# WindHack.net
KiCad netlist of a schematic drawn in EAGLE
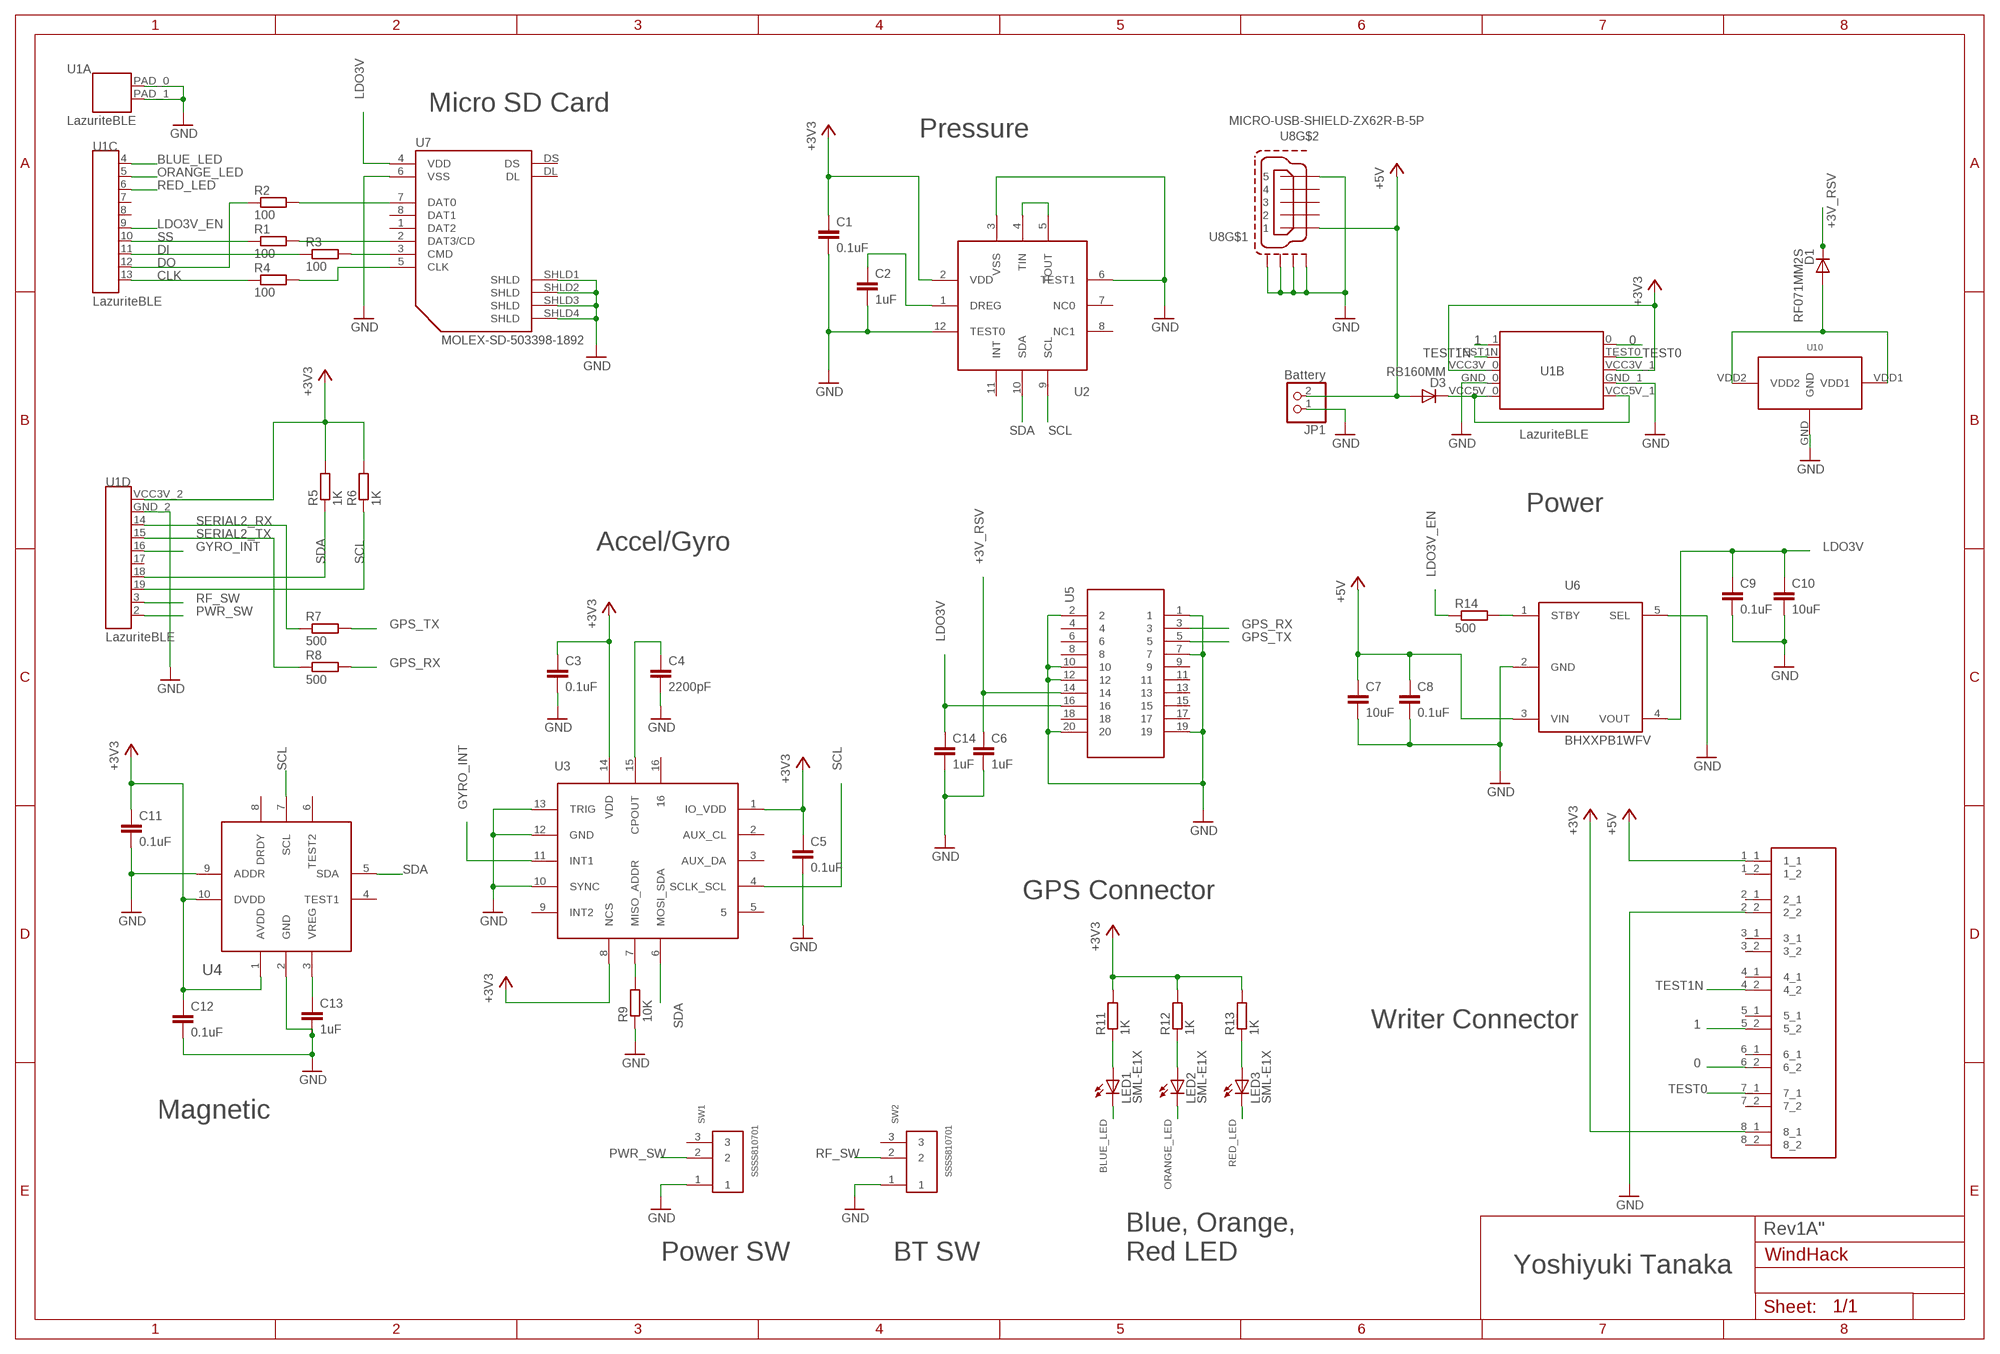
[diagram p0: schematic, sheet 1]

(export (version "E")
  (design (tool "Eeschema 10.0.6"))
  (components
    (comp (ref "C1")
      (value "0.1uF")
      (footprint "eagle-import:C0603")
      (libsource (lib "eagle-import") (part "C-EUC0603"))
    )
    (comp (ref "C2")
      (value "1uF")
      (footprint "eagle-import:C0603")
      (libsource (lib "eagle-import") (part "C-EUC0603"))
    )
    (comp (ref "C3")
      (value "0.1uF")
      (footprint "eagle-import:C0603")
      (libsource (lib "eagle-import") (part "C-EUC0603"))
    )
    (comp (ref "C4")
      (value "2200pF")
      (footprint "eagle-import:C0603")
      (libsource (lib "eagle-import") (part "C-EUC0603"))
    )
    (comp (ref "C5")
      (value "0.1uF")
      (footprint "eagle-import:C0603")
      (libsource (lib "eagle-import") (part "C-EUC0603"))
    )
    (comp (ref "C6")
      (value "1uF")
      (footprint "eagle-import:C0603")
      (libsource (lib "eagle-import") (part "C-EUC0603"))
    )
    (comp (ref "C7")
      (value "10uF")
      (footprint "eagle-import:C0603")
      (libsource (lib "eagle-import") (part "C-EUC0603"))
    )
    (comp (ref "C8")
      (value "0.1uF")
      (footprint "eagle-import:C0603")
      (libsource (lib "eagle-import") (part "C-EUC0603"))
    )
    (comp (ref "C9")
      (value "0.1uF")
      (footprint "eagle-import:C0603")
      (libsource (lib "eagle-import") (part "C-EUC0603"))
    )
    (comp (ref "C10")
      (value "10uF")
      (footprint "eagle-import:C0603")
      (libsource (lib "eagle-import") (part "C-EUC0603"))
    )
    (comp (ref "C11")
      (value "0.1uF")
      (footprint "eagle-import:C0603")
      (libsource (lib "eagle-import") (part "C-EUC0603"))
    )
    (comp (ref "C12")
      (value "0.1uF")
      (footprint "eagle-import:C0603")
      (libsource (lib "eagle-import") (part "C-EUC0603"))
    )
    (comp (ref "C13")
      (value "1uF")
      (footprint "eagle-import:C0603")
      (libsource (lib "eagle-import") (part "C-EUC0603"))
    )
    (comp (ref "C14")
      (value "1uF")
      (footprint "eagle-import:C0603")
      (libsource (lib "eagle-import") (part "C-EUC0603"))
    )
    (comp (ref "D1")
      (value "RF071MM2S")
      (footprint "eagle-import:RF071MM2S")
      (libsource (lib "eagle-import") (part "RF071MM2S"))
    )
    (comp (ref "D3")
      (value "RB160MM")
      (footprint "eagle-import:RB160MM-30")
      (libsource (lib "eagle-import") (part "RB160MM"))
    )
    (comp (ref "JP1")
      (value "Battery")
      (footprint "eagle-import:1X02")
      (libsource (lib "eagle-import") (part "PINHD-1X2"))
    )
    (comp (ref "LED1")
      (value "SML-E1X")
      (footprint "eagle-import:SML-E1X")
      (libsource (lib "eagle-import") (part "SML-E1X"))
    )
    (comp (ref "LED2")
      (value "SML-E1X")
      (footprint "eagle-import:SML-E1X")
      (libsource (lib "eagle-import") (part "SML-E1X"))
    )
    (comp (ref "LED3")
      (value "SML-E1X")
      (footprint "eagle-import:SML-E1X")
      (libsource (lib "eagle-import") (part "SML-E1X"))
    )
    (comp (ref "R1")
      (value "100")
      (footprint "eagle-import:R0603")
      (libsource (lib "eagle-import") (part "R-EU_R0603"))
    )
    (comp (ref "R2")
      (value "100")
      (footprint "eagle-import:R0603")
      (libsource (lib "eagle-import") (part "R-EU_R0603"))
    )
    (comp (ref "R3")
      (value "100")
      (footprint "eagle-import:R0603")
      (libsource (lib "eagle-import") (part "R-EU_R0603"))
    )
    (comp (ref "R4")
      (value "100")
      (footprint "eagle-import:R0603")
      (libsource (lib "eagle-import") (part "R-EU_R0603"))
    )
    (comp (ref "R5")
      (value "1K")
      (footprint "eagle-import:R0603")
      (libsource (lib "eagle-import") (part "R-EU_R0603"))
    )
    (comp (ref "R6")
      (value "1K")
      (footprint "eagle-import:R0603")
      (libsource (lib "eagle-import") (part "R-EU_R0603"))
    )
    (comp (ref "R7")
      (value "500")
      (footprint "eagle-import:R0603")
      (libsource (lib "eagle-import") (part "R-EU_R0603"))
    )
    (comp (ref "R8")
      (value "500")
      (footprint "eagle-import:R0603")
      (libsource (lib "eagle-import") (part "R-EU_R0603"))
    )
    (comp (ref "R9")
      (value "10K")
      (footprint "eagle-import:R0603")
      (libsource (lib "eagle-import") (part "R-EU_R0603"))
    )
    (comp (ref "R11")
      (value "1K")
      (footprint "eagle-import:R0603")
      (libsource (lib "eagle-import") (part "R-EU_R0603"))
    )
    (comp (ref "R12")
      (value "1K")
      (footprint "eagle-import:R0603")
      (libsource (lib "eagle-import") (part "R-EU_R0603"))
    )
    (comp (ref "R13")
      (value "1K")
      (footprint "eagle-import:R0603")
      (libsource (lib "eagle-import") (part "R-EU_R0603"))
    )
    (comp (ref "R14")
      (value "500")
      (footprint "eagle-import:R0603")
      (libsource (lib "eagle-import") (part "R-EU_R0603"))
    )
    (comp (ref "SW1")
      (value "SSSS810701")
      (footprint "eagle-import:SSSS810701")
      (libsource (lib "eagle-import") (part "SSSS810701"))
    )
    (comp (ref "SW2")
      (value "SSSS810701")
      (footprint "eagle-import:SSSS810701")
      (libsource (lib "eagle-import") (part "SSSS810701"))
    )
    (comp (ref "U$1")
      (value "XB-1-X")
      (footprint "eagle-import:XB-1-X")
      (libsource (lib "eagle-import") (part "XB-1-X"))
    )
    (comp (ref "U1")
      (value "LazuriteBLE")
      (footprint "eagle-import:LAZURITE920J")
      (libsource (lib "eagle-import") (part "LAZURITE920JLAZURITE920J"))
    )
    (comp (ref "U2")
      (value "BM1383AGLV")
      (footprint "eagle-import:BM1383AGLV")
      (libsource (lib "eagle-import") (part "BM1383AGLV"))
    )
    (comp (ref "U3")
      (value "KXG03")
      (footprint "eagle-import:KXG03")
      (libsource (lib "eagle-import") (part "KXG03"))
    )
    (comp (ref "U4")
      (value "BM1422AGMV")
      (footprint "eagle-import:BM1422AGMV")
      (libsource (lib "eagle-import") (part "BM1422AGMV"))
    )
    (comp (ref "U5")
      (value "DF40C-20DS-0.4V")
      (footprint "eagle-import:DF40C-20DS-0.4V")
      (libsource (lib "eagle-import") (part "DF40C-20DS-0.4V"))
    )
    (comp (ref "U6")
      (value "BHXXPB1WFV")
      (footprint "eagle-import:HVSOF5")
      (libsource (lib "eagle-import") (part "BHXXPB1WFV"))
    )
    (comp (ref "U7")
      (value "MOLEX-SD-503398-1892")
      (footprint "eagle-import:MOLEX-SD-503398-003")
      (libsource (lib "eagle-import") (part "MOLEX-SD-503398-1892"))
    )
    (comp (ref "U8")
      (value "MICRO-USB-SHIELD-ZX62R-B-5P")
      (footprint "eagle-import:ZX62R-B-5P")
      (libsource (lib "eagle-import") (part "MICRO-USB-SHIELD-ZX62R-B-5P"))
    )
    (comp (ref "U10")
      (value "BK-913")
      (footprint "eagle-import:BK-913")
      (libsource (lib "eagle-import") (part "BK-913"))
    )
  )
  (nets
    (net (code "1") (name "+3V3") (class "Default")
      (node (ref "C1") (pin "1") (pinfunction "1_1") (pintype "passive"))
      (node (ref "C11") (pin "1") (pinfunction "1_1") (pintype "passive"))
      (node (ref "C12") (pin "1") (pinfunction "1_1") (pintype "passive"))
      (node (ref "C3") (pin "1") (pinfunction "1_1") (pintype "passive"))
      (node (ref "C5") (pin "1") (pinfunction "1_1") (pintype "passive"))
      (node (ref "R11") (pin "2") (pinfunction "2_2") (pintype "passive"))
      (node (ref "R12") (pin "2") (pinfunction "2_2") (pintype "passive"))
      (node (ref "R13") (pin "2") (pinfunction "2_2") (pintype "passive"))
      (node (ref "R5") (pin "2") (pinfunction "2_2") (pintype "passive"))
      (node (ref "R6") (pin "2") (pinfunction "2_2") (pintype "passive"))
      (node (ref "U$1") (pin "8_1") (pinfunction "8_1_8_1") (pintype "bidirectional"))
      (node (ref "U1") (pin "VCC3V_0") (pinfunction "VCC3V_0_VCC3V_0") (pintype "passive"))
      (node (ref "U1") (pin "VCC3V_1") (pinfunction "VCC3V_1_VCC3V_1") (pintype "passive"))
      (node (ref "U1") (pin "VCC3V_2") (pinfunction "VCC3V_2_VCC3V_2") (pintype "passive"))
      (node (ref "U2") (pin "2") (pinfunction "VDD_2") (pintype "power_in"))
      (node (ref "U3") (pin "1") (pinfunction "IO_VDD_1") (pintype "power_in"))
      (node (ref "U3") (pin "14") (pinfunction "VDD_14") (pintype "power_in"))
      (node (ref "U3") (pin "8") (pinfunction "NCS_8") (pintype "bidirectional"))
      (node (ref "U4") (pin "1") (pinfunction "AVDD_1") (pintype "power_in"))
      (node (ref "U4") (pin "10") (pinfunction "DVDD_10") (pintype "power_in"))
    )
    (net (code "2") (name "+5V") (class "Default")
      (node (ref "C7") (pin "1") (pinfunction "1_1") (pintype "passive"))
      (node (ref "C8") (pin "1") (pinfunction "1_1") (pintype "passive"))
      (node (ref "D3") (pin "A") (pinfunction "A_A") (pintype "passive"))
      (node (ref "JP1") (pin "2") (pinfunction "2_2") (pintype "passive"))
      (node (ref "U$1") (pin "1_1") (pinfunction "1_1_1_1") (pintype "bidirectional"))
      (node (ref "U6") (pin "3") (pinfunction "VIN_3") (pintype "bidirectional"))
      (node (ref "U8") (pin "1") (pinfunction "1_1") (pintype "input"))
    )
    (net (code "3") (name "/+3V_RSV") (class "Default")
      (node (ref "C6") (pin "1") (pinfunction "1_1") (pintype "passive"))
      (node (ref "D1") (pin "C") (pinfunction "C_C") (pintype "passive"))
      (node (ref "U5") (pin "14") (pinfunction "14_14") (pintype "bidirectional"))
    )
    (net (code "4") (name "/0") (class "Default")
      (node (ref "U$1") (pin "6_2") (pinfunction "6_2_6_2") (pintype "bidirectional"))
      (node (ref "U1") (pin "0") (pinfunction "0_0") (pintype "passive"))
    )
    (net (code "5") (name "/1") (class "Default")
      (node (ref "U$1") (pin "5_2") (pinfunction "5_2_5_2") (pintype "bidirectional"))
      (node (ref "U1") (pin "1") (pinfunction "1_1") (pintype "passive"))
    )
    (net (code "6") (name "/BLUE_LED") (class "Default")
      (node (ref "LED1") (pin "C") (pinfunction "C_C") (pintype "passive"))
      (node (ref "U1") (pin "4") (pinfunction "4_4") (pintype "passive"))
    )
    (net (code "7") (name "/CLK") (class "Default")
      (node (ref "R4") (pin "1") (pinfunction "1_1") (pintype "passive"))
      (node (ref "U1") (pin "13") (pinfunction "13_13") (pintype "passive"))
    )
    (net (code "8") (name "/DI") (class "Default")
      (node (ref "R3") (pin "1") (pinfunction "1_1") (pintype "passive"))
      (node (ref "U1") (pin "11") (pinfunction "11_11") (pintype "passive"))
    )
    (net (code "9") (name "/DO") (class "Default")
      (node (ref "R2") (pin "1") (pinfunction "1_1") (pintype "passive"))
      (node (ref "U1") (pin "12") (pinfunction "12_12") (pintype "passive"))
    )
    (net (code "10") (name "/GPS_RX") (class "Default")
      (node (ref "R8") (pin "2") (pinfunction "2_2") (pintype "passive"))
      (node (ref "U5") (pin "3") (pinfunction "3_3") (pintype "bidirectional"))
    )
    (net (code "11") (name "/GPS_TX") (class "Default")
      (node (ref "R7") (pin "2") (pinfunction "2_2") (pintype "passive"))
      (node (ref "U5") (pin "5") (pinfunction "5_5") (pintype "bidirectional"))
    )
    (net (code "12") (name "/GYRO_INT") (class "Default")
      (node (ref "U1") (pin "16") (pinfunction "16_16") (pintype "passive"))
      (node (ref "U3") (pin "11") (pinfunction "INT1_11") (pintype "output"))
    )
    (net (code "13") (name "/LDO3V") (class "Default")
      (node (ref "C10") (pin "1") (pinfunction "1_1") (pintype "passive"))
      (node (ref "C14") (pin "1") (pinfunction "1_1") (pintype "passive"))
      (node (ref "C9") (pin "1") (pinfunction "1_1") (pintype "passive"))
      (node (ref "U5") (pin "16") (pinfunction "16_16") (pintype "bidirectional"))
      (node (ref "U6") (pin "4") (pinfunction "VOUT_4") (pintype "bidirectional"))
      (node (ref "U7") (pin "4") (pinfunction "VDD_4") (pintype "power_in"))
    )
    (net (code "14") (name "/LDO3V_EN") (class "Default")
      (node (ref "R14") (pin "1") (pinfunction "1_1") (pintype "passive"))
      (node (ref "U1") (pin "9") (pinfunction "9_9") (pintype "passive"))
    )
    (net (code "15") (name "/ORANGE_LED") (class "Default")
      (node (ref "LED2") (pin "C") (pinfunction "C_C") (pintype "passive"))
      (node (ref "U1") (pin "5") (pinfunction "5_5") (pintype "passive"))
    )
    (net (code "16") (name "/PWR_SW") (class "Default")
      (node (ref "SW1") (pin "2") (pinfunction "2_2") (pintype "bidirectional"))
      (node (ref "U1") (pin "2") (pinfunction "2_2") (pintype "passive"))
    )
    (net (code "17") (name "/RED_LED") (class "Default")
      (node (ref "LED3") (pin "C") (pinfunction "C_C") (pintype "passive"))
      (node (ref "U1") (pin "6") (pinfunction "6_6") (pintype "passive"))
    )
    (net (code "18") (name "/RF_SW") (class "Default")
      (node (ref "SW2") (pin "2") (pinfunction "2_2") (pintype "bidirectional"))
      (node (ref "U1") (pin "3") (pinfunction "3_3") (pintype "passive"))
    )
    (net (code "19") (name "/SCL") (class "Default")
      (node (ref "R6") (pin "1") (pinfunction "1_1") (pintype "passive"))
      (node (ref "U1") (pin "19") (pinfunction "19_19") (pintype "passive"))
      (node (ref "U2") (pin "9") (pinfunction "SCL_9") (pintype "bidirectional"))
      (node (ref "U3") (pin "4") (pinfunction "SCLK_SCL_4") (pintype "input"))
      (node (ref "U4") (pin "7") (pinfunction "SCL_7") (pintype "input"))
    )
    (net (code "20") (name "/SDA") (class "Default")
      (node (ref "R5") (pin "1") (pinfunction "1_1") (pintype "passive"))
      (node (ref "U1") (pin "18") (pinfunction "18_18") (pintype "passive"))
      (node (ref "U2") (pin "10") (pinfunction "SDA_10") (pintype "bidirectional"))
      (node (ref "U3") (pin "6") (pinfunction "MOSI_SDA_6") (pintype "bidirectional"))
      (node (ref "U4") (pin "5") (pinfunction "SDA_5") (pintype "bidirectional"))
    )
    (net (code "21") (name "/SERIAL2_RX") (class "Default")
      (node (ref "R7") (pin "1") (pinfunction "1_1") (pintype "passive"))
      (node (ref "U1") (pin "14") (pinfunction "14_14") (pintype "passive"))
    )
    (net (code "22") (name "/SERIAL2_TX") (class "Default")
      (node (ref "R8") (pin "1") (pinfunction "1_1") (pintype "passive"))
      (node (ref "U1") (pin "15") (pinfunction "15_15") (pintype "passive"))
    )
    (net (code "23") (name "/SS") (class "Default")
      (node (ref "R1") (pin "1") (pinfunction "1_1") (pintype "passive"))
      (node (ref "U1") (pin "10") (pinfunction "10_10") (pintype "passive"))
    )
    (net (code "24") (name "/TEST0") (class "Default")
      (node (ref "U$1") (pin "7_1") (pinfunction "7_1_7_1") (pintype "bidirectional"))
      (node (ref "U1") (pin "TEST0") (pinfunction "TEST0_TEST0") (pintype "passive"))
    )
    (net (code "25") (name "/TEST1N") (class "Default")
      (node (ref "U$1") (pin "4_2") (pinfunction "4_2_4_2") (pintype "bidirectional"))
      (node (ref "U1") (pin "TEST1N") (pinfunction "TEST1N_TEST1N") (pintype "passive"))
    )
    (net (code "26") (name "GND") (class "Default")
      (node (ref "C1") (pin "2") (pinfunction "2_2") (pintype "passive"))
      (node (ref "C10") (pin "2") (pinfunction "2_2") (pintype "passive"))
      (node (ref "C11") (pin "2") (pinfunction "2_2") (pintype "passive"))
      (node (ref "C12") (pin "2") (pinfunction "2_2") (pintype "passive"))
      (node (ref "C13") (pin "2") (pinfunction "2_2") (pintype "passive"))
      (node (ref "C14") (pin "2") (pinfunction "2_2") (pintype "passive"))
      (node (ref "C2") (pin "2") (pinfunction "2_2") (pintype "passive"))
      (node (ref "C3") (pin "2") (pinfunction "2_2") (pintype "passive"))
      (node (ref "C4") (pin "2") (pinfunction "2_2") (pintype "passive"))
      (node (ref "C5") (pin "2") (pinfunction "2_2") (pintype "passive"))
      (node (ref "C6") (pin "2") (pinfunction "2_2") (pintype "passive"))
      (node (ref "C7") (pin "2") (pinfunction "2_2") (pintype "passive"))
      (node (ref "C8") (pin "2") (pinfunction "2_2") (pintype "passive"))
      (node (ref "C9") (pin "2") (pinfunction "2_2") (pintype "passive"))
      (node (ref "JP1") (pin "1") (pinfunction "1_1") (pintype "passive"))
      (node (ref "R9") (pin "1") (pinfunction "1_1") (pintype "passive"))
      (node (ref "SW1") (pin "1") (pinfunction "1_1") (pintype "bidirectional"))
      (node (ref "SW2") (pin "1") (pinfunction "1_1") (pintype "bidirectional"))
      (node (ref "U$1") (pin "2_2") (pinfunction "2_2_2_2") (pintype "bidirectional"))
      (node (ref "U1") (pin "GND_0") (pinfunction "GND_0_GND_0") (pintype "passive"))
      (node (ref "U1") (pin "GND_1") (pinfunction "GND_1_GND_1") (pintype "passive"))
      (node (ref "U1") (pin "GND_2") (pinfunction "GND_2_GND_2") (pintype "passive"))
      (node (ref "U1") (pin "PAD_0") (pinfunction "PAD_0_PAD_0") (pintype "passive"))
      (node (ref "U1") (pin "PAD_1") (pinfunction "PAD_1_PAD_1") (pintype "passive"))
      (node (ref "U10") (pin "GND") (pinfunction "GND_GND") (pintype "power_in"))
      (node (ref "U2") (pin "12") (pinfunction "TEST0_12") (pintype "bidirectional"))
      (node (ref "U2") (pin "3") (pinfunction "VSS_3") (pintype "power_in"))
      (node (ref "U2") (pin "6") (pinfunction "TEST1_6") (pintype "bidirectional"))
      (node (ref "U3") (pin "10") (pinfunction "SYNC_10") (pintype "bidirectional"))
      (node (ref "U3") (pin "12") (pinfunction "GND_12") (pintype "power_in"))
      (node (ref "U3") (pin "13") (pinfunction "TRIG_13") (pintype "input"))
      (node (ref "U4") (pin "2") (pinfunction "GND_2") (pintype "power_in"))
      (node (ref "U4") (pin "9") (pinfunction "ADDR_9") (pintype "input"))
      (node (ref "U5") (pin "1") (pinfunction "1_1") (pintype "bidirectional"))
      (node (ref "U5") (pin "10") (pinfunction "10_10") (pintype "bidirectional"))
      (node (ref "U5") (pin "12") (pinfunction "12_12") (pintype "bidirectional"))
      (node (ref "U5") (pin "19") (pinfunction "19_19") (pintype "bidirectional"))
      (node (ref "U5") (pin "2") (pinfunction "2_2") (pintype "bidirectional"))
      (node (ref "U5") (pin "20") (pinfunction "20_20") (pintype "bidirectional"))
      (node (ref "U5") (pin "7") (pinfunction "7_7") (pintype "bidirectional"))
      (node (ref "U6") (pin "2") (pinfunction "GND_2") (pintype "bidirectional"))
      (node (ref "U6") (pin "5") (pinfunction "SEL_5") (pintype "bidirectional"))
      (node (ref "U7") (pin "6") (pinfunction "VSS_6") (pintype "power_in"))
      (node (ref "U7") (pin "SHLD1") (pinfunction "SHLD_SHLD1") (pintype "power_in"))
      (node (ref "U7") (pin "SHLD2") (pinfunction "SHLD_SHLD2") (pintype "power_in"))
      (node (ref "U7") (pin "SHLD3") (pinfunction "SHLD_SHLD3") (pintype "power_in"))
      (node (ref "U7") (pin "SHLD4") (pinfunction "SHLD_SHLD4") (pintype "power_in"))
      (node (ref "U8") (pin "5") (pinfunction "5_5") (pintype "input"))
      (node (ref "U8") (pin "M1") (pinfunction "S1_M1") (pintype "passive"))
      (node (ref "U8") (pin "M2") (pinfunction "S2_M2") (pintype "passive"))
      (node (ref "U8") (pin "M3") (pinfunction "S3_M3") (pintype "passive"))
      (node (ref "U8") (pin "M4") (pinfunction "S4_M4") (pintype "passive"))
    )
    (net (code "27") (name "Net-(D1-PadA)") (class "Default")
      (node (ref "D1") (pin "A") (pinfunction "A_A") (pintype "passive"))
      (node (ref "U10") (pin "VDD1") (pinfunction "VDD1_VDD1") (pintype "power_in"))
      (node (ref "U10") (pin "VDD2") (pinfunction "VDD2_VDD2") (pintype "power_in"))
    )
    (net (code "28") (name "Net-(D3-PadC)") (class "Default")
      (node (ref "D3") (pin "C") (pinfunction "C_C") (pintype "passive"))
      (node (ref "U1") (pin "VCC5V_0") (pinfunction "VCC5V_0_VCC5V_0") (pintype "passive"))
      (node (ref "U1") (pin "VCC5V_1") (pinfunction "VCC5V_1_VCC5V_1") (pintype "passive"))
    )
    (net (code "29") (name "Net-(LED1-PadA)") (class "Default")
      (node (ref "LED1") (pin "A") (pinfunction "A_A") (pintype "passive"))
      (node (ref "R11") (pin "1") (pinfunction "1_1") (pintype "passive"))
    )
    (net (code "30") (name "Net-(LED2-PadA)") (class "Default")
      (node (ref "LED2") (pin "A") (pinfunction "A_A") (pintype "passive"))
      (node (ref "R12") (pin "1") (pinfunction "1_1") (pintype "passive"))
    )
    (net (code "31") (name "Net-(LED3-PadA)") (class "Default")
      (node (ref "LED3") (pin "A") (pinfunction "A_A") (pintype "passive"))
      (node (ref "R13") (pin "1") (pinfunction "1_1") (pintype "passive"))
    )
    (net (code "32") (name "Net-(U2-DREG)") (class "Default")
      (node (ref "C2") (pin "1") (pinfunction "1_1") (pintype "passive"))
      (node (ref "U2") (pin "1") (pinfunction "DREG_1") (pintype "bidirectional"))
    )
    (net (code "33") (name "Net-(U2-TIN)") (class "Default")
      (node (ref "U2") (pin "4") (pinfunction "TIN_4") (pintype "input"))
      (node (ref "U2") (pin "5") (pinfunction "TOUT_5") (pintype "output"))
    )
    (net (code "34") (name "Net-(U3-CPOUT)") (class "Default")
      (node (ref "C4") (pin "1") (pinfunction "1_1") (pintype "passive"))
      (node (ref "U3") (pin "15") (pinfunction "CPOUT_15") (pintype "bidirectional"))
    )
    (net (code "35") (name "Net-(U3-MISO_ADDR)") (class "Default")
      (node (ref "R9") (pin "2") (pinfunction "2_2") (pintype "passive"))
      (node (ref "U3") (pin "7") (pinfunction "MISO_ADDR_7") (pintype "bidirectional"))
    )
    (net (code "36") (name "Net-(U4-VREG)") (class "Default")
      (node (ref "C13") (pin "1") (pinfunction "1_1") (pintype "passive"))
      (node (ref "U4") (pin "3") (pinfunction "VREG_3") (pintype "output"))
    )
    (net (code "37") (name "Net-(U6-STBY)") (class "Default")
      (node (ref "R14") (pin "2") (pinfunction "2_2") (pintype "passive"))
      (node (ref "U6") (pin "1") (pinfunction "STBY_1") (pintype "bidirectional"))
    )
    (net (code "38") (name "Net-(U7-CLK)") (class "Default")
      (node (ref "R4") (pin "2") (pinfunction "2_2") (pintype "passive"))
      (node (ref "U7") (pin "5") (pinfunction "CLK_5") (pintype "bidirectional"))
    )
    (net (code "39") (name "Net-(U7-CMD)") (class "Default")
      (node (ref "R3") (pin "2") (pinfunction "2_2") (pintype "passive"))
      (node (ref "U7") (pin "3") (pinfunction "CMD_3") (pintype "bidirectional"))
    )
    (net (code "40") (name "Net-(U7-DAT0)") (class "Default")
      (node (ref "R2") (pin "2") (pinfunction "2_2") (pintype "passive"))
      (node (ref "U7") (pin "7") (pinfunction "DAT0_7") (pintype "bidirectional"))
    )
    (net (code "41") (name "Net-(U7-DAT3{slash}CD)") (class "Default")
      (node (ref "R1") (pin "2") (pinfunction "2_2") (pintype "passive"))
      (node (ref "U7") (pin "2") (pinfunction "DAT3/CD_2") (pintype "bidirectional"))
    )
    (net (code "42") (name "unconnected-(SW1-Pad3)") (class "Default")
      (node (ref "SW1") (pin "3") (pinfunction "3_3") (pintype "bidirectional"))
    )
    (net (code "43") (name "unconnected-(SW2-Pad3)") (class "Default")
      (node (ref "SW2") (pin "3") (pinfunction "3_3") (pintype "bidirectional"))
    )
    (net (code "44") (name "unconnected-(U$1-Pad1_2)") (class "Default")
      (node (ref "U$1") (pin "1_2") (pinfunction "1_2_1_2") (pintype "bidirectional"))
    )
    (net (code "45") (name "unconnected-(U$1-Pad2_1)") (class "Default")
      (node (ref "U$1") (pin "2_1") (pinfunction "2_1_2_1") (pintype "bidirectional"))
    )
    (net (code "46") (name "unconnected-(U$1-Pad3_1)") (class "Default")
      (node (ref "U$1") (pin "3_1") (pinfunction "3_1_3_1") (pintype "bidirectional"))
    )
    (net (code "47") (name "unconnected-(U$1-Pad3_2)") (class "Default")
      (node (ref "U$1") (pin "3_2") (pinfunction "3_2_3_2") (pintype "bidirectional"))
    )
    (net (code "48") (name "unconnected-(U$1-Pad4_1)") (class "Default")
      (node (ref "U$1") (pin "4_1") (pinfunction "4_1_4_1") (pintype "bidirectional"))
    )
    (net (code "49") (name "unconnected-(U$1-Pad5_1)") (class "Default")
      (node (ref "U$1") (pin "5_1") (pinfunction "5_1_5_1") (pintype "bidirectional"))
    )
    (net (code "50") (name "unconnected-(U$1-Pad6_1)") (class "Default")
      (node (ref "U$1") (pin "6_1") (pinfunction "6_1_6_1") (pintype "bidirectional"))
    )
    (net (code "51") (name "unconnected-(U$1-Pad7_2)") (class "Default")
      (node (ref "U$1") (pin "7_2") (pinfunction "7_2_7_2") (pintype "bidirectional"))
    )
    (net (code "52") (name "unconnected-(U$1-Pad8_2)") (class "Default")
      (node (ref "U$1") (pin "8_2") (pinfunction "8_2_8_2") (pintype "bidirectional"))
    )
    (net (code "53") (name "unconnected-(U1-Pad7)") (class "Default")
      (node (ref "U1") (pin "7") (pinfunction "7_7") (pintype "passive"))
    )
    (net (code "54") (name "unconnected-(U1-Pad8)") (class "Default")
      (node (ref "U1") (pin "8") (pinfunction "8_8") (pintype "passive"))
    )
    (net (code "55") (name "unconnected-(U1-Pad17)") (class "Default")
      (node (ref "U1") (pin "17") (pinfunction "17_17") (pintype "passive"))
    )
    (net (code "56") (name "unconnected-(U2-INT-Pad11)") (class "Default")
      (node (ref "U2") (pin "11") (pinfunction "INT_11") (pintype "output"))
    )
    (net (code "57") (name "unconnected-(U2-NC0-Pad7)") (class "Default")
      (node (ref "U2") (pin "7") (pinfunction "NC0_7") (pintype "no_connect"))
    )
    (net (code "58") (name "unconnected-(U2-NC1-Pad8)") (class "Default")
      (node (ref "U2") (pin "8") (pinfunction "NC1_8") (pintype "no_connect"))
    )
    (net (code "59") (name "unconnected-(U3-AUX_CL-Pad2)") (class "Default")
      (node (ref "U3") (pin "2") (pinfunction "AUX_CL_2") (pintype "input"))
    )
    (net (code "60") (name "unconnected-(U3-AUX_DA-Pad3)") (class "Default")
      (node (ref "U3") (pin "3") (pinfunction "AUX_DA_3") (pintype "bidirectional"))
    )
    (net (code "61") (name "unconnected-(U3-INT2-Pad9)") (class "Default")
      (node (ref "U3") (pin "9") (pinfunction "INT2_9") (pintype "output"))
    )
    (net (code "62") (name "unconnected-(U3-Pad5)") (class "Default")
      (node (ref "U3") (pin "5") (pinfunction "5_5") (pintype "no_connect"))
    )
    (net (code "63") (name "unconnected-(U3-Pad16)") (class "Default")
      (node (ref "U3") (pin "16") (pinfunction "16_16") (pintype "no_connect"))
    )
    (net (code "64") (name "unconnected-(U4-DRDY-Pad8)") (class "Default")
      (node (ref "U4") (pin "8") (pinfunction "DRDY_8") (pintype "output"))
    )
    (net (code "65") (name "unconnected-(U4-TEST1-Pad4)") (class "Default")
      (node (ref "U4") (pin "4") (pinfunction "TEST1_4") (pintype "no_connect"))
    )
    (net (code "66") (name "unconnected-(U4-TEST2-Pad6)") (class "Default")
      (node (ref "U4") (pin "6") (pinfunction "TEST2_6") (pintype "no_connect"))
    )
    (net (code "67") (name "unconnected-(U5-Pad4)") (class "Default")
      (node (ref "U5") (pin "4") (pinfunction "4_4") (pintype "bidirectional"))
    )
    (net (code "68") (name "unconnected-(U5-Pad6)") (class "Default")
      (node (ref "U5") (pin "6") (pinfunction "6_6") (pintype "bidirectional"))
    )
    (net (code "69") (name "unconnected-(U5-Pad8)") (class "Default")
      (node (ref "U5") (pin "8") (pinfunction "8_8") (pintype "bidirectional"))
    )
    (net (code "70") (name "unconnected-(U5-Pad9)") (class "Default")
      (node (ref "U5") (pin "9") (pinfunction "9_9") (pintype "bidirectional"))
    )
    (net (code "71") (name "unconnected-(U5-Pad11)") (class "Default")
      (node (ref "U5") (pin "11") (pinfunction "11_11") (pintype "bidirectional"))
    )
    (net (code "72") (name "unconnected-(U5-Pad13)") (class "Default")
      (node (ref "U5") (pin "13") (pinfunction "13_13") (pintype "bidirectional"))
    )
    (net (code "73") (name "unconnected-(U5-Pad15)") (class "Default")
      (node (ref "U5") (pin "15") (pinfunction "15_15") (pintype "bidirectional"))
    )
    (net (code "74") (name "unconnected-(U5-Pad17)") (class "Default")
      (node (ref "U5") (pin "17") (pinfunction "17_17") (pintype "bidirectional"))
    )
    (net (code "75") (name "unconnected-(U5-Pad18)") (class "Default")
      (node (ref "U5") (pin "18") (pinfunction "18_18") (pintype "bidirectional"))
    )
    (net (code "76") (name "unconnected-(U7-DAT1-Pad8)") (class "Default")
      (node (ref "U7") (pin "8") (pinfunction "DAT1_8") (pintype "bidirectional"))
    )
    (net (code "77") (name "unconnected-(U7-DAT2-Pad1)") (class "Default")
      (node (ref "U7") (pin "1") (pinfunction "DAT2_1") (pintype "bidirectional"))
    )
    (net (code "78") (name "unconnected-(U7-PadDL)") (class "Default")
      (node (ref "U7") (pin "DL") (pinfunction "DL_DL") (pintype "passive"))
    )
    (net (code "79") (name "unconnected-(U7-PadDS)") (class "Default")
      (node (ref "U7") (pin "DS") (pinfunction "DS_DS") (pintype "passive"))
    )
    (net (code "80") (name "unconnected-(U8-Pad2)") (class "Default")
      (node (ref "U8") (pin "2") (pinfunction "2_2") (pintype "input"))
    )
    (net (code "81") (name "unconnected-(U8-Pad3)") (class "Default")
      (node (ref "U8") (pin "3") (pinfunction "3_3") (pintype "input"))
    )
    (net (code "82") (name "unconnected-(U8-Pad4)") (class "Default")
      (node (ref "U8") (pin "4") (pinfunction "4_4") (pintype "input"))
    )
  )
)
